# lm3410-sepic-led-driver-17mm-mk-2.net
KiCad netlist of a schematic drawn in EAGLE
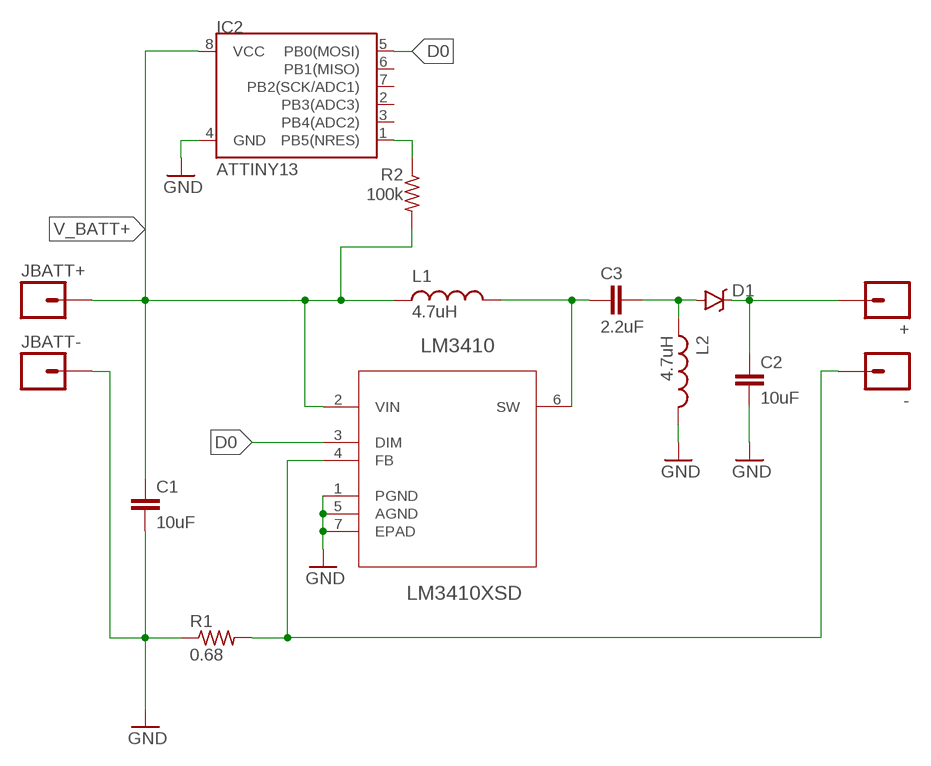
[diagram p0: schematic, sheet 1]

(export (version "E")
  (design (tool "Eeschema 10.0.6"))
  (components
    (comp (ref "+")
      (value "M01PTH-KIT")
      (footprint "eagle-import:1X01-KIT")
      (libsource (lib "eagle-import") (part "M01PTH-KIT"))
    )
    (comp (ref "-")
      (value "M01NOSILK-KIT")
      (footprint "eagle-import:1X01NS-KIT")
      (libsource (lib "eagle-import") (part "M01NOSILK-KIT"))
    )
    (comp (ref "C1")
      (value "10uF")
      (footprint "eagle-import:C0603")
      (libsource (lib "eagle-import") (part "CAPACITOR-CERAMICC0603"))
    )
    (comp (ref "C2")
      (value "10uF")
      (footprint "eagle-import:C0603")
      (libsource (lib "eagle-import") (part "CAPACITOR-CERAMICC0603"))
    )
    (comp (ref "C3")
      (value "2.2uF")
      (footprint "eagle-import:C0805")
      (libsource (lib "eagle-import") (part "CAPACITOR-CERAMICC0805"))
    )
    (comp (ref "D1")
      (value "BAT20J")
      (footprint "eagle-import:SOD-323")
      (libsource (lib "eagle-import") (part "DIODE-SCHOTTKYBAT20J"))
    )
    (comp (ref "IC2")
      (value "ATTINY13")
      (footprint "eagle-import:SO08")
      (libsource (lib "eagle-import") (part "ATTINY13SOIC"))
    )
    (comp (ref "JBATT+")
      (value "M01NOT-A-VIA-NOPE")
      (footprint "eagle-import:1X01_NOSILK_NOSTOP")
      (libsource (lib "eagle-import") (part "M01NOT-A-VIA-NOPE"))
    )
    (comp (ref "JBATT-")
      (value "M01NOT-A-VIA-NOPE")
      (footprint "eagle-import:1X01_NOSILK_NOSTOP")
      (libsource (lib "eagle-import") (part "M01NOT-A-VIA-NOPE"))
    )
    (comp (ref "L1")
      (value "4.7uH")
      (footprint "eagle-import:INDUCTOR_2X1.6MM")
      (libsource (lib "eagle-import") (part "INDUCTORIFSC-0806"))
    )
    (comp (ref "L2")
      (value "4.7uH")
      (footprint "eagle-import:INDUCTOR_2X1.6MM")
      (libsource (lib "eagle-import") (part "INDUCTORIFSC-0806"))
    )
    (comp (ref "LM3410")
      (value "LM3410XSD")
      (footprint "eagle-import:DFN300X300X80-7N")
      (libsource (lib "eagle-import") (part "LM3410XSD"))
    )
    (comp (ref "R1")
      (value "0.68")
      (footprint "eagle-import:R1206")
      (libsource (lib "eagle-import") (part "RESISTORR1206"))
    )
    (comp (ref "R2")
      (value "100k")
      (footprint "eagle-import:R0402")
      (libsource (lib "eagle-import") (part "RESISTORR0402"))
    )
  )
  (nets
    (net (code "1") (name "D0") (class "Default")
      (node (ref "IC2") (pin "5") (pinfunction "PB0(MOSI)_5") (pintype "bidirectional"))
      (node (ref "LM3410") (pin "3") (pinfunction "DIM_3") (pintype "input"))
    )
    (net (code "2") (name "GND") (class "Default")
      (node (ref "C1") (pin "2") (pinfunction "2_2") (pintype "passive"))
      (node (ref "C2") (pin "2") (pinfunction "2_2") (pintype "passive"))
      (node (ref "IC2") (pin "4") (pinfunction "GND_4") (pintype "bidirectional"))
      (node (ref "JBATT-") (pin "P$1") (pinfunction "1_P$1") (pintype "passive"))
      (node (ref "L2") (pin "P$2") (pinfunction "2_P$2") (pintype "passive"))
      (node (ref "LM3410") (pin "1") (pinfunction "PGND_1") (pintype "passive"))
      (node (ref "LM3410") (pin "5") (pinfunction "AGND_5") (pintype "passive"))
      (node (ref "LM3410") (pin "7") (pinfunction "EPAD_7") (pintype "passive"))
      (node (ref "R1") (pin "1") (pinfunction "1_1") (pintype "passive"))
    )
    (net (code "3") (name "Net-(+-Pad1)") (class "Default")
      (node (ref "+") (pin "1") (pinfunction "1_1") (pintype "passive"))
      (node (ref "C2") (pin "1") (pinfunction "1_1") (pintype "passive"))
      (node (ref "D1") (pin "C") (pinfunction "C_C") (pintype "passive"))
    )
    (net (code "4") (name "Net-(IC2-PB5(NRES))") (class "Default")
      (node (ref "IC2") (pin "1") (pinfunction "PB5(NRES)_1") (pintype "bidirectional"))
      (node (ref "R2") (pin "1") (pinfunction "1_1") (pintype "passive"))
    )
    (net (code "5") (name "Net-(L1-2)") (class "Default")
      (node (ref "C3") (pin "1") (pinfunction "1_1") (pintype "passive"))
      (node (ref "L1") (pin "P$2") (pinfunction "2_P$2") (pintype "passive"))
      (node (ref "LM3410") (pin "6") (pinfunction "SW_6") (pintype "output"))
    )
    (net (code "6") (name "Net-(L2-1)") (class "Default")
      (node (ref "C3") (pin "2") (pinfunction "2_2") (pintype "passive"))
      (node (ref "D1") (pin "A") (pinfunction "A_A") (pintype "passive"))
      (node (ref "L2") (pin "P$1") (pinfunction "1_P$1") (pintype "passive"))
    )
    (net (code "7") (name "Net-(LM3410-FB)") (class "Default")
      (node (ref "-") (pin "1") (pinfunction "1_1") (pintype "passive"))
      (node (ref "LM3410") (pin "4") (pinfunction "FB_4") (pintype "input"))
      (node (ref "R1") (pin "2") (pinfunction "2_2") (pintype "passive"))
    )
    (net (code "8") (name "V_BATT+") (class "Default")
      (node (ref "C1") (pin "1") (pinfunction "1_1") (pintype "passive"))
      (node (ref "IC2") (pin "8") (pinfunction "VCC_8") (pintype "bidirectional"))
      (node (ref "JBATT+") (pin "P$1") (pinfunction "1_P$1") (pintype "passive"))
      (node (ref "L1") (pin "P$1") (pinfunction "1_P$1") (pintype "passive"))
      (node (ref "LM3410") (pin "2") (pinfunction "VIN_2") (pintype "power_in"))
      (node (ref "R2") (pin "2") (pinfunction "2_2") (pintype "passive"))
    )
    (net (code "9") (name "unconnected-(IC2-PB1(MISO)-Pad6)") (class "Default")
      (node (ref "IC2") (pin "6") (pinfunction "PB1(MISO)_6") (pintype "bidirectional"))
    )
    (net (code "10") (name "unconnected-(IC2-PB2(SCK{slash}ADC1)-Pad7)") (class "Default")
      (node (ref "IC2") (pin "7") (pinfunction "PB2(SCK/ADC1)_7") (pintype "bidirectional"))
    )
    (net (code "11") (name "unconnected-(IC2-PB3(ADC3)-Pad2)") (class "Default")
      (node (ref "IC2") (pin "2") (pinfunction "PB3(ADC3)_2") (pintype "bidirectional"))
    )
    (net (code "12") (name "unconnected-(IC2-PB4(ADC2)-Pad3)") (class "Default")
      (node (ref "IC2") (pin "3") (pinfunction "PB4(ADC2)_3") (pintype "bidirectional"))
    )
  )
)
